# Buttons.net
KiCad netlist of a schematic drawn in Altium Designer
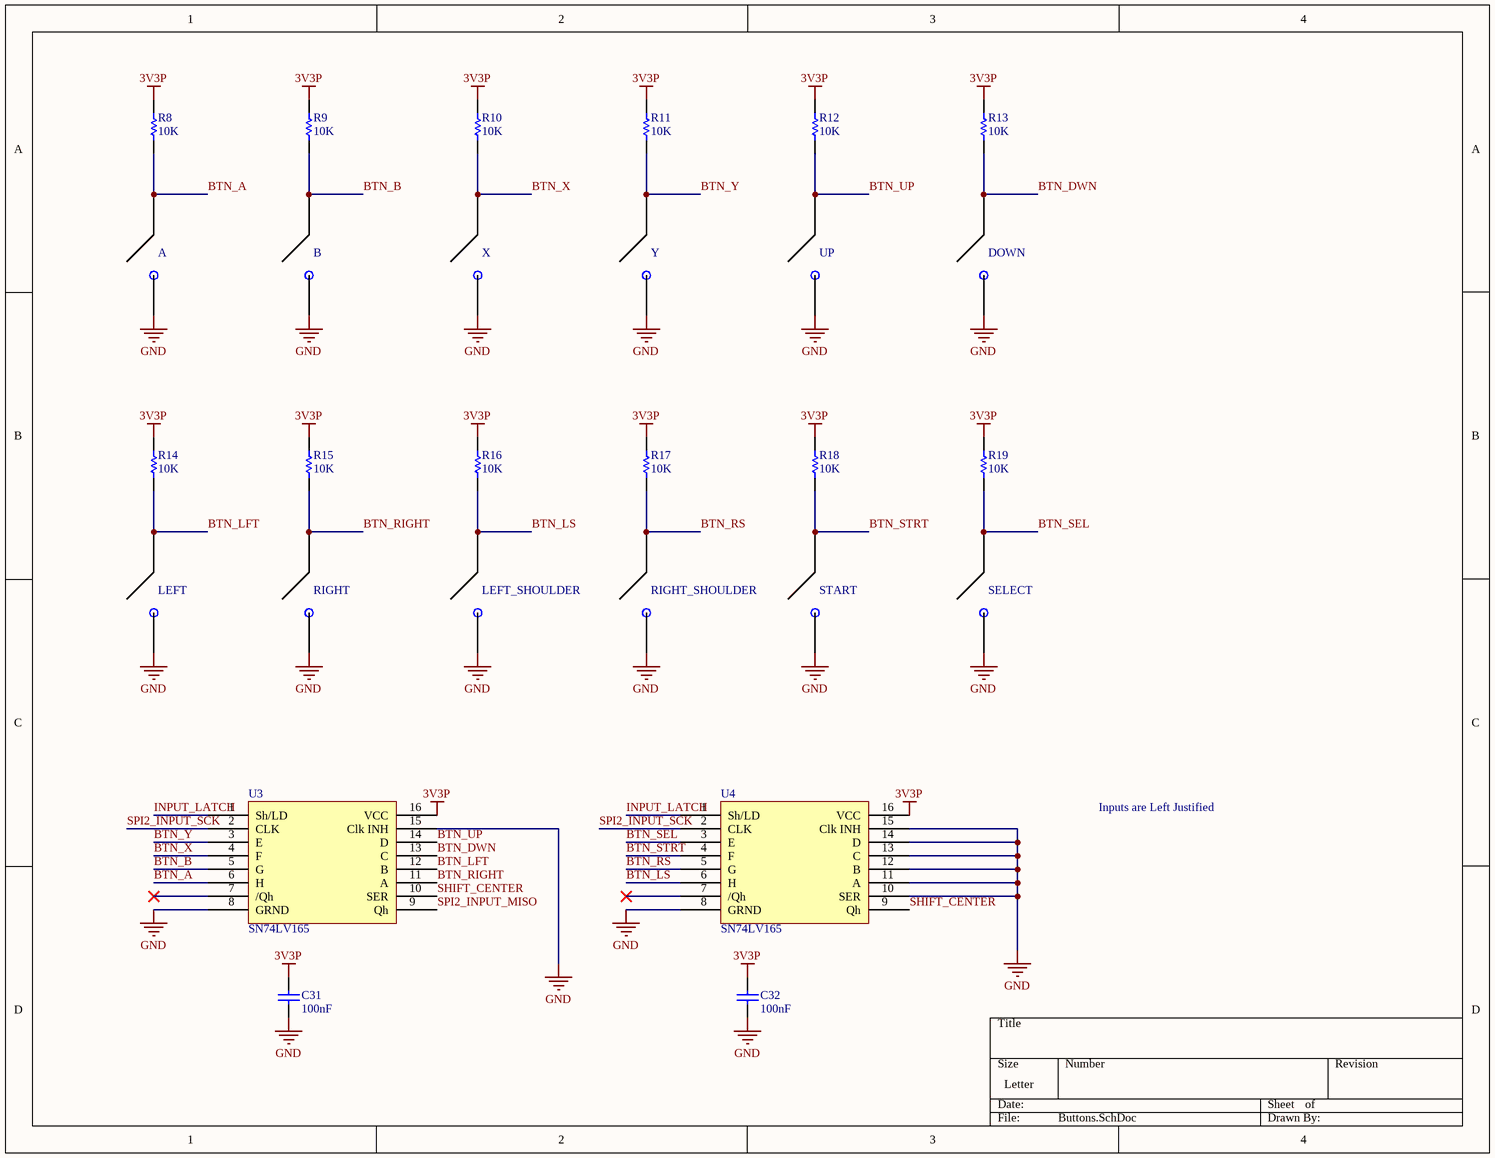
[diagram p0: Buttons.SchDoc]

(export (version "E")
  (design (tool "Eeschema 10.0.6"))
  (components
    (comp (ref "A") (value "12mmBTN") (footprint "SMT12mmbutton") (libsource (lib "") (part "12mmBTN_1")))
    (comp (ref "B") (value "12mmBTN") (footprint "SMT12mmbutton") (libsource (lib "") (part "12mmBTN_1")))
    (comp (ref "C31")
      (value "100nF")
      (footprint "C0805")
      (description "Capacitor")
      (fields (field (name "PUBLISHER") "Altium Limited"))
      (libsource (lib "Miscellaneous Devices") (part "Cap"))
    )
    (comp (ref "C32")
      (value "100nF")
      (footprint "C0805")
      (description "Capacitor")
      (fields (field (name "PUBLISHER") "Altium Limited"))
      (libsource (lib "Miscellaneous Devices") (part "Cap"))
    )
    (comp (ref "DOWN") (value "12mmBTN") (footprint "SMT12mmbutton") (libsource (lib "") (part "12mmBTN_1")))
    (comp (ref "LEFT") (value "12mmBTN") (footprint "SMT12mmbutton") (libsource (lib "") (part "12mmBTN_1")))
    (comp (ref "LEFT_SHOULDER")
      (value "12mmBTN")
      (footprint "HDR1X2")
      (libsource (lib "GameMan") (part "12mmBTN"))
    )
    (comp (ref "R8")
      (value "10K")
      (footprint "6-0805_M")
      (description "Resistor")
      (fields (field (name "PUBLISHER") "Altium Limited"))
      (libsource (lib "Miscellaneous Devices") (part "Res1"))
    )
    (comp (ref "R9")
      (value "10K")
      (footprint "6-0805_M")
      (description "Resistor")
      (fields (field (name "PUBLISHER") "Altium Limited"))
      (libsource (lib "Miscellaneous Devices") (part "Res1"))
    )
    (comp (ref "R10")
      (value "10K")
      (footprint "6-0805_M")
      (description "Resistor")
      (fields (field (name "PUBLISHER") "Altium Limited"))
      (libsource (lib "Miscellaneous Devices") (part "Res1"))
    )
    (comp (ref "R11")
      (value "10K")
      (footprint "6-0805_M")
      (description "Resistor")
      (fields (field (name "PUBLISHER") "Altium Limited"))
      (libsource (lib "Miscellaneous Devices") (part "Res1"))
    )
    (comp (ref "R12")
      (value "10K")
      (footprint "6-0805_M")
      (description "Resistor")
      (fields (field (name "PUBLISHER") "Altium Limited"))
      (libsource (lib "Miscellaneous Devices") (part "Res1"))
    )
    (comp (ref "R13")
      (value "10K")
      (footprint "6-0805_M")
      (description "Resistor")
      (fields (field (name "PUBLISHER") "Altium Limited"))
      (libsource (lib "Miscellaneous Devices") (part "Res1"))
    )
    (comp (ref "R14")
      (value "10K")
      (footprint "6-0805_M")
      (description "Resistor")
      (fields (field (name "PUBLISHER") "Altium Limited"))
      (libsource (lib "Miscellaneous Devices") (part "Res1"))
    )
    (comp (ref "R15")
      (value "10K")
      (footprint "6-0805_M")
      (description "Resistor")
      (fields (field (name "PUBLISHER") "Altium Limited"))
      (libsource (lib "Miscellaneous Devices") (part "Res1"))
    )
    (comp (ref "R16")
      (value "10K")
      (footprint "6-0805_M")
      (description "Resistor")
      (fields (field (name "PUBLISHER") "Altium Limited"))
      (libsource (lib "Miscellaneous Devices") (part "Res1"))
    )
    (comp (ref "R17")
      (value "10K")
      (footprint "6-0805_M")
      (description "Resistor")
      (fields (field (name "PUBLISHER") "Altium Limited"))
      (libsource (lib "Miscellaneous Devices") (part "Res1"))
    )
    (comp (ref "R18")
      (value "10K")
      (footprint "6-0805_M")
      (description "Resistor")
      (fields (field (name "PUBLISHER") "Altium Limited"))
      (libsource (lib "Miscellaneous Devices") (part "Res1"))
    )
    (comp (ref "R19")
      (value "10K")
      (footprint "6-0805_M")
      (description "Resistor")
      (fields (field (name "PUBLISHER") "Altium Limited"))
      (libsource (lib "Miscellaneous Devices") (part "Res1"))
    )
    (comp (ref "RIGHT") (value "12mmBTN") (footprint "SMT12mmbutton") (libsource (lib "") (part "12mmBTN_1")))
    (comp (ref "RIGHT_SHOULDER")
      (value "12mmBTN")
      (footprint "HDR1X2")
      (libsource (lib "GameMan") (part "12mmBTN"))
    )
    (comp (ref "SELECT")
      (value "12mmBTN")
      (footprint "SMT12mmbutton")
      (libsource (lib "") (part "12mmBTN_1"))
    )
    (comp (ref "START") (value "12mmBTN") (footprint "SMT12mmbutton") (libsource (lib "") (part "12mmBTN_1")))
    (comp (ref "U3")
      (value "SN74LV165")
      (footprint "SOP16_Hand")
      (libsource (lib "GameMan_SchLib") (part "SN74LV165"))
    )
    (comp (ref "U4")
      (value "SN74LV165")
      (footprint "SOP16_Hand")
      (libsource (lib "GameMan_SchLib") (part "SN74LV165"))
    )
    (comp (ref "UP") (value "12mmBTN") (footprint "SMT12mmbutton") (libsource (lib "") (part "12mmBTN_1")))
    (comp (ref "X") (value "12mmBTN") (footprint "SMT12mmbutton") (libsource (lib "") (part "12mmBTN_1")))
    (comp (ref "Y") (value "12mmBTN") (footprint "SMT12mmbutton") (libsource (lib "") (part "12mmBTN_1")))
  )
  (nets
    (net (code "1") (name "/BTN_A") (class "Default")
      (node (ref "A") (pin "1") (pinfunction "1_1") (pintype "passive"))
      (node (ref "R8") (pin "2") (pinfunction "2_2") (pintype "passive"))
      (node (ref "U3") (pin "6") (pinfunction "H_6") (pintype "passive"))
    )
    (net (code "2") (name "/BTN_B") (class "Default")
      (node (ref "B") (pin "1") (pinfunction "1_1") (pintype "passive"))
      (node (ref "R9") (pin "2") (pinfunction "2_2") (pintype "passive"))
      (node (ref "U3") (pin "5") (pinfunction "G_5") (pintype "passive"))
    )
    (net (code "3") (name "/BTN_DWN") (class "Default")
      (node (ref "DOWN") (pin "1") (pinfunction "1_1") (pintype "passive"))
      (node (ref "R13") (pin "2") (pinfunction "2_2") (pintype "passive"))
      (node (ref "U3") (pin "13") (pinfunction "C_13") (pintype "passive"))
    )
    (net (code "4") (name "/BTN_LFT") (class "Default")
      (node (ref "LEFT") (pin "1") (pinfunction "1_1") (pintype "passive"))
      (node (ref "R14") (pin "2") (pinfunction "2_2") (pintype "passive"))
      (node (ref "U3") (pin "12") (pinfunction "B_12") (pintype "passive"))
    )
    (net (code "5") (name "/BTN_LS") (class "Default")
      (node (ref "LEFT_SHOULDER") (pin "2") (pinfunction "1_2") (pintype "passive"))
      (node (ref "R16") (pin "2") (pinfunction "2_2") (pintype "passive"))
      (node (ref "U4") (pin "6") (pinfunction "H_6") (pintype "passive"))
    )
    (net (code "6") (name "/BTN_RIGHT") (class "Default")
      (node (ref "R15") (pin "2") (pinfunction "2_2") (pintype "passive"))
      (node (ref "RIGHT") (pin "1") (pinfunction "1_1") (pintype "passive"))
      (node (ref "U3") (pin "11") (pinfunction "A_11") (pintype "passive"))
    )
    (net (code "7") (name "/BTN_RS") (class "Default")
      (node (ref "R17") (pin "2") (pinfunction "2_2") (pintype "passive"))
      (node (ref "RIGHT_SHOULDER") (pin "2") (pinfunction "1_2") (pintype "passive"))
      (node (ref "U4") (pin "5") (pinfunction "G_5") (pintype "passive"))
    )
    (net (code "8") (name "/BTN_SEL") (class "Default")
      (node (ref "R19") (pin "2") (pinfunction "2_2") (pintype "passive"))
      (node (ref "SELECT") (pin "1") (pinfunction "1_1") (pintype "passive"))
      (node (ref "U4") (pin "3") (pinfunction "E_3") (pintype "passive"))
    )
    (net (code "9") (name "/BTN_STRT") (class "Default")
      (node (ref "R18") (pin "2") (pinfunction "2_2") (pintype "passive"))
      (node (ref "START") (pin "1") (pinfunction "1_1") (pintype "passive"))
      (node (ref "U4") (pin "4") (pinfunction "F_4") (pintype "passive"))
    )
    (net (code "10") (name "/BTN_UP") (class "Default")
      (node (ref "R12") (pin "2") (pinfunction "2_2") (pintype "passive"))
      (node (ref "U3") (pin "14") (pinfunction "D_14") (pintype "passive"))
      (node (ref "UP") (pin "1") (pinfunction "1_1") (pintype "passive"))
    )
    (net (code "11") (name "/BTN_X") (class "Default")
      (node (ref "R10") (pin "2") (pinfunction "2_2") (pintype "passive"))
      (node (ref "U3") (pin "4") (pinfunction "F_4") (pintype "passive"))
      (node (ref "X") (pin "1") (pinfunction "1_1") (pintype "passive"))
    )
    (net (code "12") (name "/BTN_Y") (class "Default")
      (node (ref "R11") (pin "2") (pinfunction "2_2") (pintype "passive"))
      (node (ref "U3") (pin "3") (pinfunction "E_3") (pintype "passive"))
      (node (ref "Y") (pin "1") (pinfunction "1_1") (pintype "passive"))
    )
    (net (code "13") (name "/INPUT_LATCH") (class "Default")
      (node (ref "U3") (pin "1") (pinfunction "Sh/LD_1") (pintype "passive"))
      (node (ref "U4") (pin "1") (pinfunction "Sh/LD_1") (pintype "passive"))
    )
    (net (code "14") (name "/SHIFT_CENTER") (class "Default")
      (node (ref "U3") (pin "10") (pinfunction "SER_10") (pintype "passive"))
      (node (ref "U4") (pin "9") (pinfunction "Qh_9") (pintype "passive"))
    )
    (net (code "15") (name "/SPI2_INPUT_MISO") (class "Default")
      (node (ref "U3") (pin "9") (pinfunction "Qh_9") (pintype "passive"))
    )
    (net (code "16") (name "/SPI2_INPUT_SCK") (class "Default")
      (node (ref "U3") (pin "2") (pinfunction "CLK_2") (pintype "passive"))
      (node (ref "U4") (pin "2") (pinfunction "CLK_2") (pintype "passive"))
    )
    (net (code "17") (name "3V3P") (class "Default")
      (node (ref "C31") (pin "2") (pinfunction "2_2") (pintype "passive"))
      (node (ref "C32") (pin "2") (pinfunction "2_2") (pintype "passive"))
      (node (ref "R10") (pin "1") (pinfunction "1_1") (pintype "passive"))
      (node (ref "R11") (pin "1") (pinfunction "1_1") (pintype "passive"))
      (node (ref "R12") (pin "1") (pinfunction "1_1") (pintype "passive"))
      (node (ref "R13") (pin "1") (pinfunction "1_1") (pintype "passive"))
      (node (ref "R14") (pin "1") (pinfunction "1_1") (pintype "passive"))
      (node (ref "R15") (pin "1") (pinfunction "1_1") (pintype "passive"))
      (node (ref "R16") (pin "1") (pinfunction "1_1") (pintype "passive"))
      (node (ref "R17") (pin "1") (pinfunction "1_1") (pintype "passive"))
      (node (ref "R18") (pin "1") (pinfunction "1_1") (pintype "passive"))
      (node (ref "R19") (pin "1") (pinfunction "1_1") (pintype "passive"))
      (node (ref "R8") (pin "1") (pinfunction "1_1") (pintype "passive"))
      (node (ref "R9") (pin "1") (pinfunction "1_1") (pintype "passive"))
      (node (ref "U3") (pin "16") (pinfunction "VCC_16") (pintype "passive"))
      (node (ref "U4") (pin "16") (pinfunction "VCC_16") (pintype "passive"))
    )
    (net (code "18") (name "GND") (class "Default")
      (node (ref "A") (pin "0") (pinfunction "0_0") (pintype "passive"))
      (node (ref "B") (pin "0") (pinfunction "0_0") (pintype "passive"))
      (node (ref "C31") (pin "1") (pinfunction "1_1") (pintype "passive"))
      (node (ref "C32") (pin "1") (pinfunction "1_1") (pintype "passive"))
      (node (ref "DOWN") (pin "0") (pinfunction "0_0") (pintype "passive"))
      (node (ref "LEFT") (pin "0") (pinfunction "0_0") (pintype "passive"))
      (node (ref "LEFT_SHOULDER") (pin "1") (pinfunction "0_1") (pintype "passive"))
      (node (ref "RIGHT") (pin "0") (pinfunction "0_0") (pintype "passive"))
      (node (ref "RIGHT_SHOULDER") (pin "1") (pinfunction "0_1") (pintype "passive"))
      (node (ref "SELECT") (pin "0") (pinfunction "0_0") (pintype "passive"))
      (node (ref "START") (pin "0") (pinfunction "0_0") (pintype "passive"))
      (node (ref "U3") (pin "15") (pinfunction "Clk_INH_15") (pintype "passive"))
      (node (ref "U3") (pin "8") (pinfunction "GRND_8") (pintype "passive"))
      (node (ref "U4") (pin "10") (pinfunction "SER_10") (pintype "passive"))
      (node (ref "U4") (pin "11") (pinfunction "A_11") (pintype "passive"))
      (node (ref "U4") (pin "12") (pinfunction "B_12") (pintype "passive"))
      (node (ref "U4") (pin "13") (pinfunction "C_13") (pintype "passive"))
      (node (ref "U4") (pin "14") (pinfunction "D_14") (pintype "passive"))
      (node (ref "U4") (pin "15") (pinfunction "Clk_INH_15") (pintype "passive"))
      (node (ref "U4") (pin "8") (pinfunction "GRND_8") (pintype "passive"))
      (node (ref "UP") (pin "0") (pinfunction "0_0") (pintype "passive"))
      (node (ref "X") (pin "0") (pinfunction "0_0") (pintype "passive"))
      (node (ref "Y") (pin "0") (pinfunction "0_0") (pintype "passive"))
    )
    (net (code "19") (name "unconnected-(U3-{slash}Qh-Pad7)") (class "Default")
      (node (ref "U3") (pin "7") (pinfunction "/Qh_7") (pintype "passive+no_connect"))
    )
    (net (code "20") (name "unconnected-(U4-{slash}Qh-Pad7)") (class "Default")
      (node (ref "U4") (pin "7") (pinfunction "/Qh_7") (pintype "passive+no_connect"))
    )
  )
)
